# MCP73831-BREAKOUT.net
KiCad netlist of a schematic drawn in Altium Designer
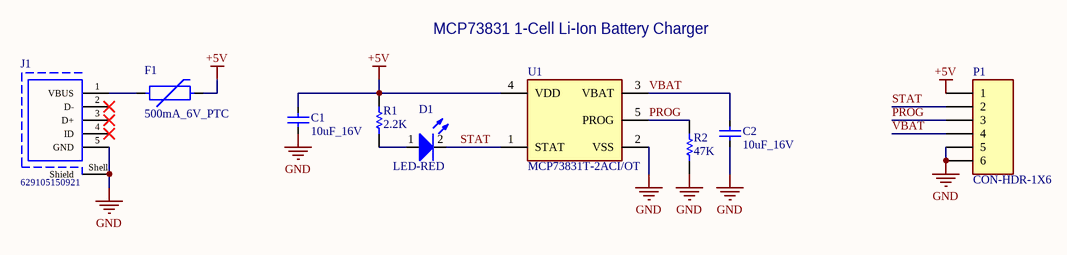
[diagram p0: MCP73831-BREAKOUT.SchDoc]

(export (version "E")
  (design (tool "Eeschema 10.0.6"))
  (components
    (comp (ref "C1")
      (value "10uF_16V")
      (footprint "CustomLib-Package:C0805")
      (description "C0805 0.10 μF X7R 30ppm/°C 10.00% 50 V")
      (fields
        (field (name "MANUFACTURER") "KEMET")
        (field (name "MANUFACTURER PART NUMBER") "C0805C104K5RAC7411")
      )
      (libsource (lib "CustomLib-Package") (part "CAPACITOR"))
    )
    (comp (ref "C2")
      (value "10uF_16V")
      (footprint "CustomLib-Package:C0805")
      (description "C0805 0.10 μF X7R 30ppm/°C 10.00% 50 V")
      (fields
        (field (name "MANUFACTURER") "KEMET")
        (field (name "MANUFACTURER PART NUMBER") "C0805C104K5RAC7411")
      )
      (libsource (lib "CustomLib-Package") (part "CAPACITOR"))
    )
    (comp (ref "D1")
      (value "LED-RED")
      (footprint "LED0805")
      (description "Typical LED")
      (libsource (lib "CustomLib-Package") (part "LED"))
    )
    (comp (ref "F1")
      (value "500mA_6V_PTC")
      (footprint "R0805")
      (description "FUSE 500MA SMD (0805) RESETABLE")
      (fields (field (name "Comment") "MF-PSMF050X-2"))
      (libsource (lib "CustomLib-Package") (part "FUSE-PTC"))
    )
    (comp (ref "J1")
      (value "629105150921")
      (footprint "CON-MICRO-USB-B-SMD-WITH-HOLDER")
      (description "Micro USB 2.0 Type AB Receptacle WR-COM, Horizontal, SMT")
      (fields (field (name "MANUFACTURER") "Wurth Elektronik") (field (name "PUBLISHER") "WurthElektronik"))
      (libsource (lib "CustomLib-Package") (part "CON-MICRO-USB-AB-RCPT-SMD"))
    )
    (comp (ref "P1")
      (value "CON-HDR-1X6")
      (footprint "CON-HDR-1X6-2.54")
      (description "Pin Header, 6-Pin")
      (fields (field (name "PUBLISHER") "Altium Limited"))
      (libsource (lib "CustomLib-Package") (part "CON-HDR-1X6"))
    )
    (comp (ref "R1")
      (value "2.2K")
      (footprint "CustomLib-Package:R0805")
      (description "RES SMD 10K OHM 1% 1/8W 0805")
      (fields (field (name "TOLERANCE") "1%") (field (name "Comment") "CRG0805F10K"))
      (libsource (lib "CustomLib-Package") (part "RESISTOR"))
    )
    (comp (ref "R2")
      (value "47K")
      (footprint "CustomLib-Package:R0805")
      (description "RES SMD 10K OHM 1% 1/8W 0805")
      (fields (field (name "TOLERANCE") "1%") (field (name "Comment") "CRG0805F10K"))
      (libsource (lib "CustomLib-Package") (part "RESISTOR"))
    )
    (comp (ref "U1")
      (value "MCP73831T-2ACI/OT")
      (footprint "SOT-23-5")
      (description "IC CONTROLLR LI-ION 4.2V SOT23-5")
      (libsource (lib "CustomLib-Package") (part "MCP73831T"))
    )
  )
  (nets
    (net (code "1") (name "+5V") (class "Default")
      (node (ref "C1") (pin "1") (pinfunction "1_1") (pintype "passive"))
      (node (ref "F1") (pin "2") (pinfunction "2_2") (pintype "passive"))
      (node (ref "P1") (pin "1") (pinfunction "1_1") (pintype "passive"))
      (node (ref "R1") (pin "2") (pinfunction "2_2") (pintype "passive"))
      (node (ref "U1") (pin "4") (pinfunction "VDD_4") (pintype "power_in"))
    )
    (net (code "2") (name "/PROG") (class "Default")
      (node (ref "P1") (pin "3") (pinfunction "3_3") (pintype "passive"))
      (node (ref "R2") (pin "1") (pinfunction "1_1") (pintype "passive"))
      (node (ref "U1") (pin "5") (pinfunction "PROG_5") (pintype "passive"))
    )
    (net (code "3") (name "/STAT") (class "Default")
      (node (ref "D1") (pin "2") (pinfunction "K_2") (pintype "passive"))
      (node (ref "P1") (pin "2") (pinfunction "2_2") (pintype "passive"))
      (node (ref "U1") (pin "1") (pinfunction "STAT_1") (pintype "passive"))
    )
    (net (code "4") (name "/VBAT") (class "Default")
      (node (ref "C2") (pin "1") (pinfunction "1_1") (pintype "passive"))
      (node (ref "P1") (pin "4") (pinfunction "4_4") (pintype "passive"))
      (node (ref "U1") (pin "3") (pinfunction "VBAT_3") (pintype "power_in"))
    )
    (net (code "5") (name "GND") (class "Default")
      (node (ref "C1") (pin "2") (pinfunction "2_2") (pintype "passive"))
      (node (ref "C2") (pin "2") (pinfunction "2_2") (pintype "passive"))
      (node (ref "J1") (pin "5") (pinfunction "GND_5") (pintype "passive"))
      (node (ref "J1") (pin "Shell") (pinfunction "Shield_Shell") (pintype "passive"))
      (node (ref "P1") (pin "5") (pinfunction "5_5") (pintype "passive"))
      (node (ref "P1") (pin "6") (pinfunction "6_6") (pintype "passive"))
      (node (ref "R2") (pin "2") (pinfunction "2_2") (pintype "passive"))
      (node (ref "U1") (pin "2") (pinfunction "VSS_2") (pintype "power_in"))
    )
    (net (code "6") (name "Net-(D1-A)") (class "Default")
      (node (ref "D1") (pin "1") (pinfunction "A_1") (pintype "passive"))
      (node (ref "R1") (pin "1") (pinfunction "1_1") (pintype "passive"))
    )
    (net (code "7") (name "Net-(J1-VBUS)") (class "Default")
      (node (ref "F1") (pin "1") (pinfunction "1_1") (pintype "passive"))
      (node (ref "J1") (pin "1") (pinfunction "VBUS_1") (pintype "passive"))
    )
    (net (code "8") (name "unconnected-(J1-D+-Pad3)") (class "Default")
      (node (ref "J1") (pin "3") (pinfunction "D+_3") (pintype "passive+no_connect"))
    )
    (net (code "9") (name "unconnected-(J1-D--Pad2)") (class "Default")
      (node (ref "J1") (pin "2") (pinfunction "D-_2") (pintype "passive+no_connect"))
    )
    (net (code "10") (name "unconnected-(J1-ID-Pad4)") (class "Default")
      (node (ref "J1") (pin "4") (pinfunction "ID_4") (pintype "passive+no_connect"))
    )
  )
)
